# design.net
KiCad netlist of a schematic drawn in Altium Designer
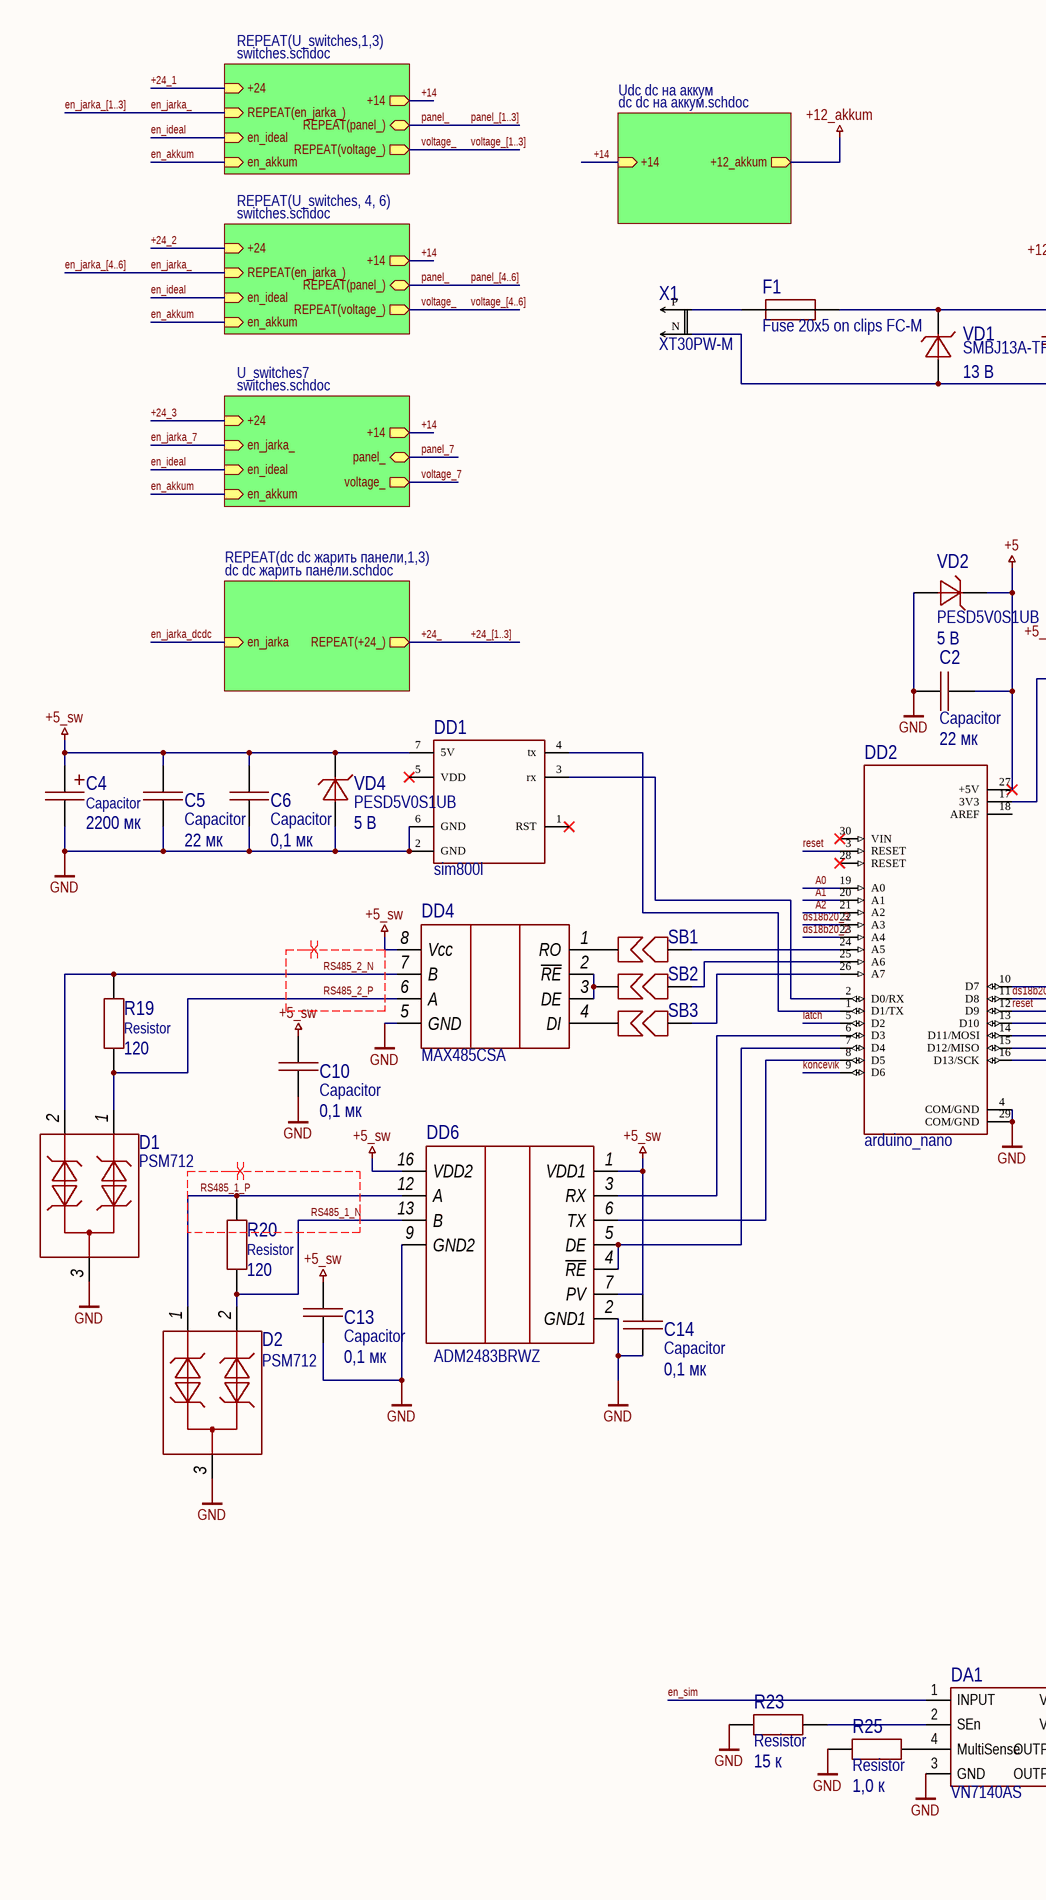
[diagram p0: хихема.SchDoc, left]
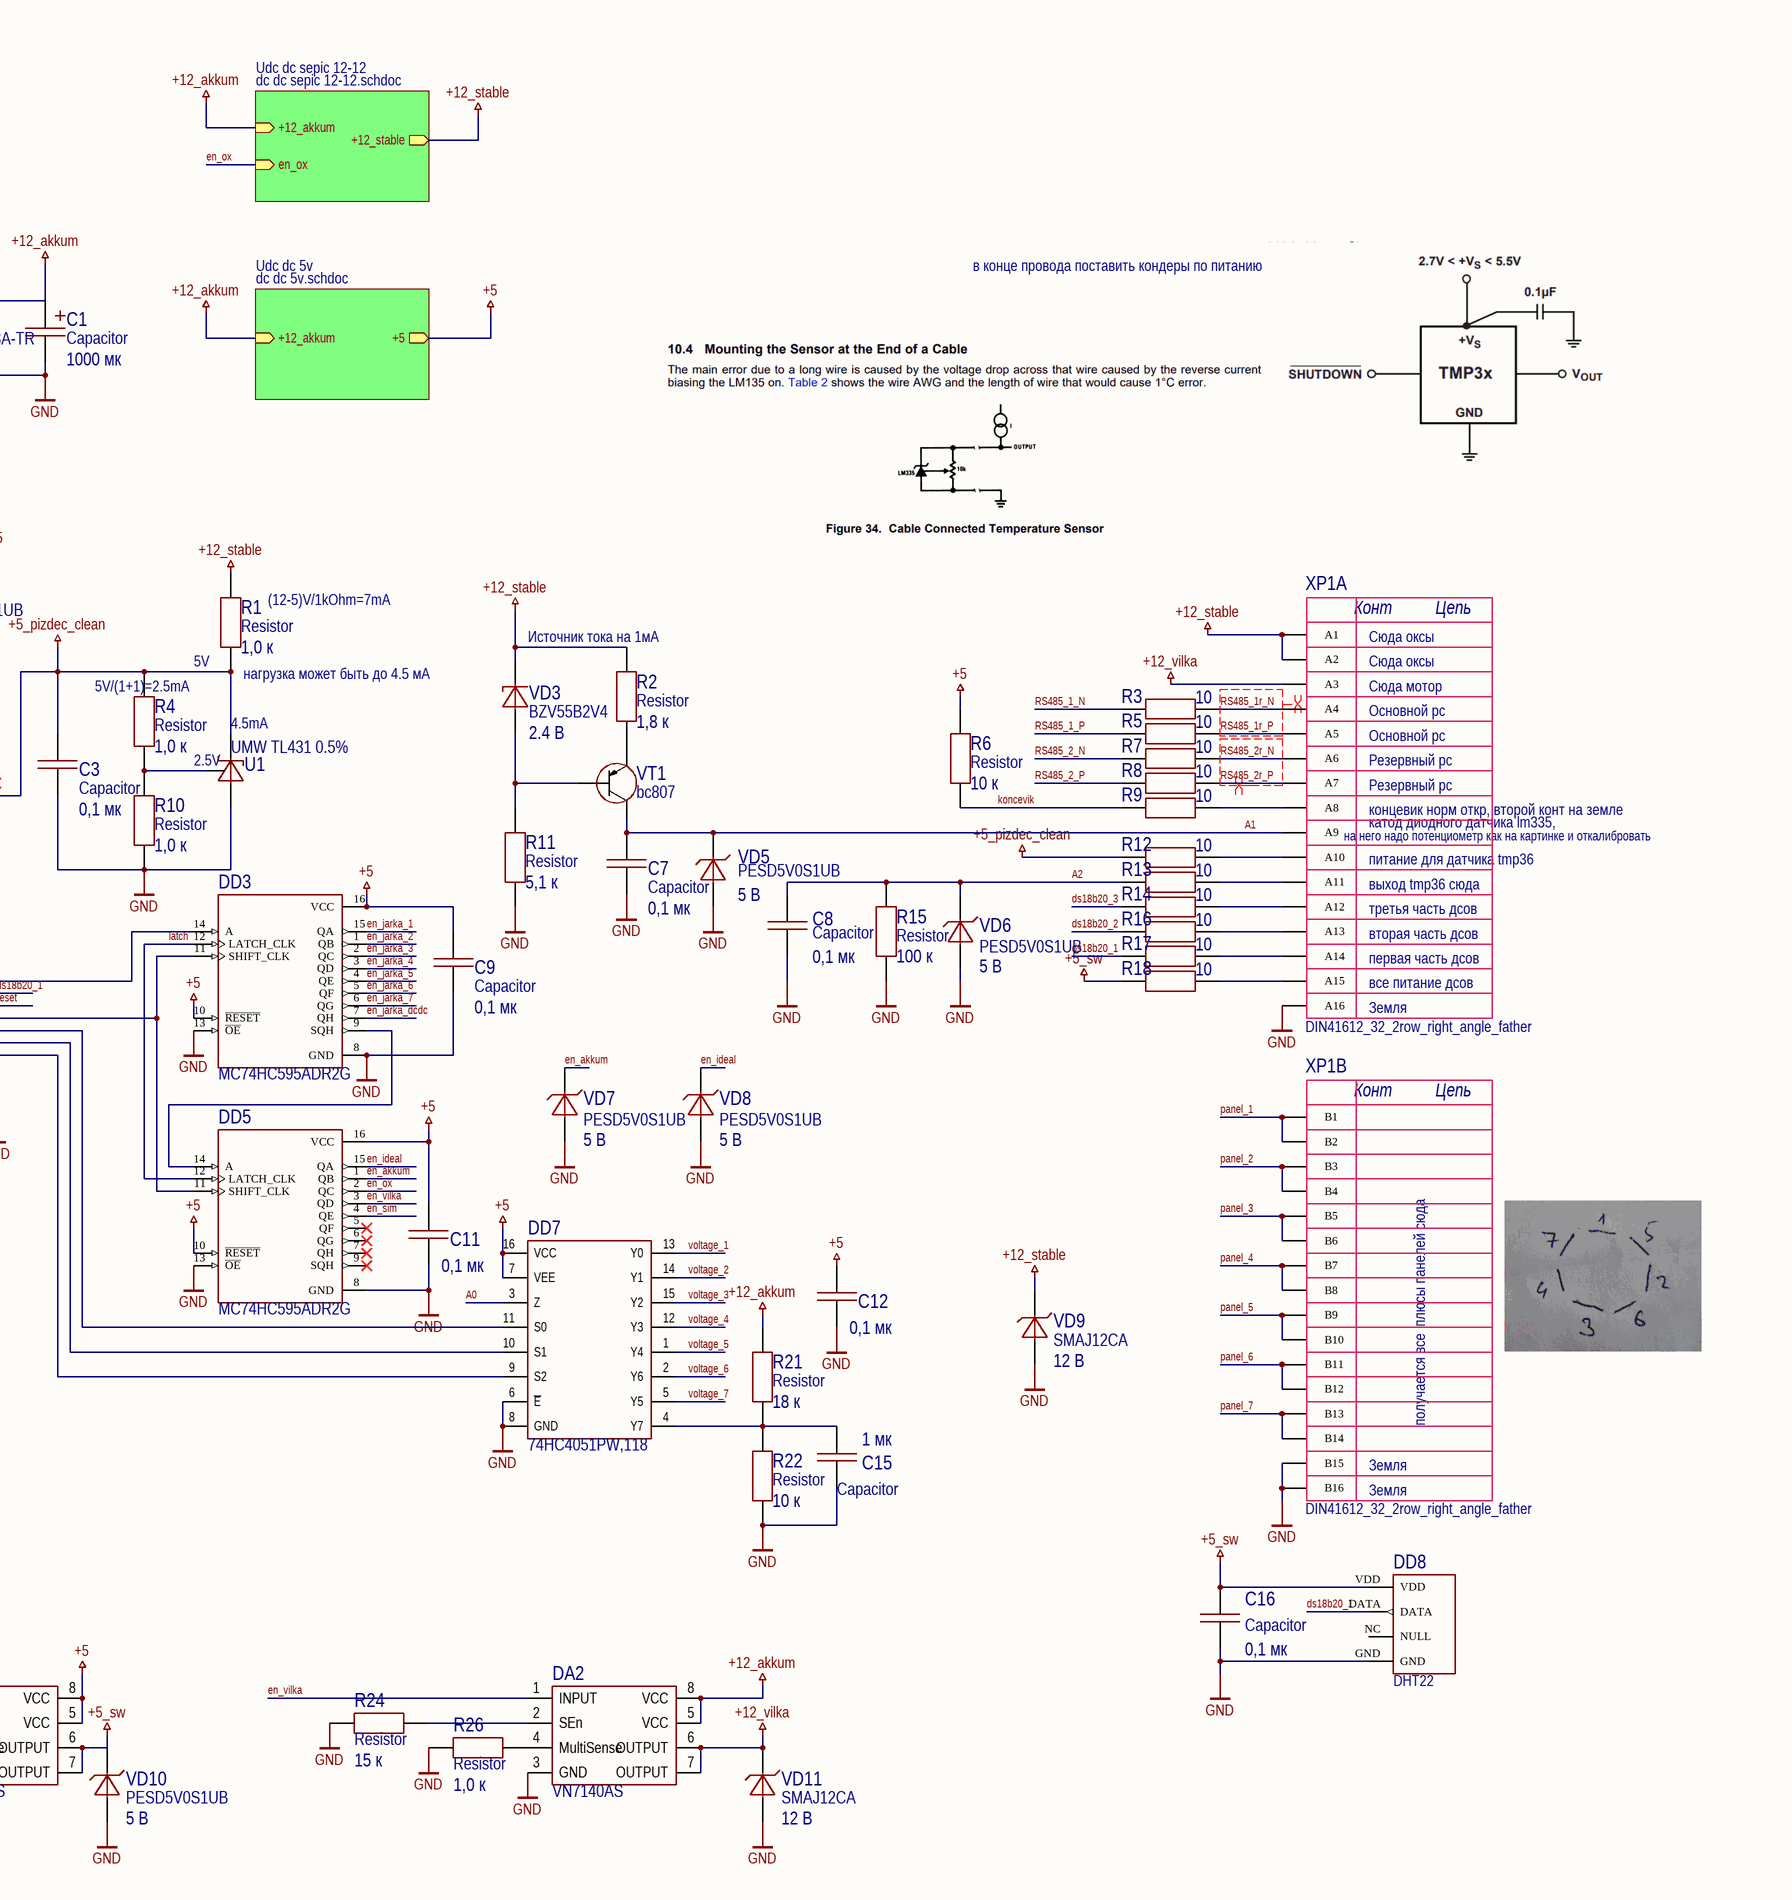
[diagram p1: хихема.SchDoc, right]

(export (version "E")
  (design (tool "Eeschema 10.0.6"))
  (components
    (comp (ref "C1")
      (value "Capacitor")
      (footprint "SMD_cap_12,5x13,5")
      (description "Конденсатор алюминиевый электролитический 1000мкФ 25В 20% Low ESR 1100мА SMD12.5x13.5мм")
      (fields
        (field (name "ALTIUM_VALUE") "1000 мк")
        (field (name "PART NUMBER") "EEVFK1E102Q")
        (field (name "TOLERANCE") "20")
      )
      (libsource (lib "Hydrolib") (part "Capacitor_polar"))
    )
    (comp (ref "C2")
      (value "Capacitor")
      (footprint "1210C")
      (description "Конденсатор")
      (fields
        (field (name "ALTIUM_VALUE") "22 мк")
        (field (name "PART NUMBER") "Capacitor_22u_10_25V_X7R_1210C")
        (field (name "TOLERANCE") "0,1")
      )
      (libsource (lib "Hydrolib") (part "Capacitor"))
    )
    (comp (ref "C3")
      (value "Capacitor")
      (footprint "0603C")
      (description "Конденсатор")
      (fields
        (field (name "ALTIUM_VALUE") "0,1 мк")
        (field (name "PART NUMBER") "Capacitor_0,1u_10_50V_X7R_0603C")
        (field (name "TOLERANCE") "0,1")
      )
      (libsource (lib "Hydrolib") (part "Capacitor"))
    )
    (comp (ref "C4")
      (value "Capacitor")
      (footprint "10x20_radial")
      (description "Конденсатор радиальный 2200мкФ 10В ±20% 10*19")
      (fields
        (field (name "ALTIUM_VALUE") "2200 мк")
        (field (name "PART NUMBER") "Capacitor_2200u_10V_10x20")
        (field (name "TOLERANCE") "20")
      )
      (libsource (lib "Hydrolib") (part "Capacitor_polar"))
    )
    (comp (ref "C5")
      (value "Capacitor")
      (footprint "1210C")
      (description "Конденсатор")
      (fields
        (field (name "ALTIUM_VALUE") "22 мк")
        (field (name "PART NUMBER") "Capacitor_22u_10_25V_X7R_1210C")
        (field (name "TOLERANCE") "0,1")
      )
      (libsource (lib "Hydrolib") (part "Capacitor"))
    )
    (comp (ref "C6")
      (value "Capacitor")
      (footprint "0603C")
      (description "Конденсатор")
      (fields
        (field (name "ALTIUM_VALUE") "0,1 мк")
        (field (name "PART NUMBER") "Capacitor_0,1u_10_50V_X7R_0603C")
        (field (name "TOLERANCE") "0,1")
      )
      (libsource (lib "Hydrolib") (part "Capacitor"))
    )
    (comp (ref "C7")
      (value "Capacitor")
      (footprint "0603C")
      (description "Конденсатор")
      (fields
        (field (name "ALTIUM_VALUE") "0,1 мк")
        (field (name "PART NUMBER") "Capacitor_0,1u_10_50V_X7R_0603C")
        (field (name "TOLERANCE") "0,1")
      )
      (libsource (lib "Hydrolib") (part "Capacitor"))
    )
    (comp (ref "C8")
      (value "Capacitor")
      (footprint "0603C")
      (description "Конденсатор")
      (fields
        (field (name "ALTIUM_VALUE") "0,1 мк")
        (field (name "PART NUMBER") "Capacitor_0,1u_10_50V_X7R_0603C")
        (field (name "TOLERANCE") "0,1")
      )
      (libsource (lib "Hydrolib") (part "Capacitor"))
    )
    (comp (ref "C9")
      (value "Capacitor")
      (footprint "0603C")
      (description "Конденсатор")
      (fields
        (field (name "ALTIUM_VALUE") "0,1 мк")
        (field (name "PART NUMBER") "Capacitor_0,1u_10_50V_X7R_0603C")
        (field (name "TOLERANCE") "0,1")
      )
      (libsource (lib "Hydrolib") (part "Capacitor"))
    )
    (comp (ref "C10")
      (value "Capacitor")
      (footprint "0603C")
      (description "Конденсатор")
      (fields
        (field (name "ALTIUM_VALUE") "0,1 мк")
        (field (name "PART NUMBER") "Capacitor_0,1u_10_50V_X7R_0603C")
        (field (name "TOLERANCE") "0,1")
      )
      (libsource (lib "Hydrolib") (part "Capacitor"))
    )
    (comp (ref "C11")
      (value "0,1 мк")
      (footprint "0603C")
      (description "Конденсатор")
      (fields (field (name "PART NUMBER") "Capacitor_0,1u_10_50V_X7R_0603C") (field (name "TOLERANCE") "0,1"))
      (libsource (lib "Hydrolib") (part "Capacitor"))
    )
    (comp (ref "C12")
      (value "0,1 мк")
      (footprint "0603C")
      (description "Конденсатор")
      (fields (field (name "PART NUMBER") "Capacitor_0,1u_10_50V_X7R_0603C") (field (name "TOLERANCE") "0,1"))
      (libsource (lib "Hydrolib") (part "Capacitor"))
    )
    (comp (ref "C13")
      (value "Capacitor")
      (footprint "0603C")
      (description "Конденсатор")
      (fields
        (field (name "ALTIUM_VALUE") "0,1 мк")
        (field (name "PART NUMBER") "Capacitor_0,1u_10_50V_X7R_0603C")
        (field (name "TOLERANCE") "0,1")
      )
      (libsource (lib "Hydrolib") (part "Capacitor"))
    )
    (comp (ref "C14")
      (value "Capacitor")
      (footprint "0603C")
      (description "Конденсатор")
      (fields
        (field (name "ALTIUM_VALUE") "0,1 мк")
        (field (name "PART NUMBER") "Capacitor_0,1u_10_50V_X7R_0603C")
        (field (name "TOLERANCE") "0,1")
      )
      (libsource (lib "Hydrolib") (part "Capacitor"))
    )
    (comp (ref "C15")
      (value "Capacitor")
      (footprint "0603C")
      (description "Конденсатор")
      (fields
        (field (name "ALTIUM_VALUE") "1 мк")
        (field (name "PART NUMBER") "Capacitor_1u_10_50V_X7R_0603C")
        (field (name "TOLERANCE") "0,1")
      )
      (libsource (lib "Hydrolib") (part "Capacitor"))
    )
    (comp (ref "C16")
      (value "Capacitor")
      (footprint "0603C")
      (description "Конденсатор")
      (fields
        (field (name "ALTIUM_VALUE") "0,1 мк")
        (field (name "PART NUMBER") "Capacitor_0,1u_10_50V_X7R_0603C")
        (field (name "TOLERANCE") "0,1")
      )
      (libsource (lib "Hydrolib") (part "Capacitor"))
    )
    (comp (ref "D1")
      (value "PSM712")
      (footprint "SOT23-3")
      (description "Защитный диод для линии RS-485")
      (libsource (lib "") (part "TVS_2_2dir_1"))
    )
    (comp (ref "D2")
      (value "PSM712")
      (footprint "SOT23-3")
      (description "Защитный диод для линии RS-485")
      (libsource (lib "Hydrolib") (part "TVS_2_2dir"))
    )
    (comp (ref "DA1")
      (value "VN7140AS")
      (footprint "SOP8")
      (description "Силовой ключ верхнего плеча с аналоговой обратной связью MultiSense автомобильного применения")
      (libsource (lib "Hydrolib") (part "VN7140AS"))
    )
    (comp (ref "DA2")
      (value "VN7140AS")
      (footprint "SOP8")
      (description "Силовой ключ верхнего плеча с аналоговой обратной связью MultiSense автомобильного применения")
      (libsource (lib "Hydrolib") (part "VN7140AS"))
    )
    (comp (ref "DD1") (value "sim800l") (footprint "sim800l") (libsource (lib "Hydrolib") (part "sim800l")))
    (comp (ref "DD2")
      (value "arduino_nano")
      (footprint "arduino_nano")
      (description "ардуинка на стойках")
      (fields (field (name "MP") "Arduino Nano") (field (name "MF") "Arduino"))
      (libsource (lib "Hydrolib") (part "ARDUINO_NANO"))
    )
    (comp (ref "DD3")
      (value "MC74HC595ADR2G")
      (footprint "SOIC-16")
      (description "8-ми битный сдвиговый регистр")
      (libsource (lib "Hydrolib") (part "MC74HC595ADR2G"))
    )
    (comp (ref "DD4")
      (value "MAX485CSA")
      (footprint "SOIC-8")
      (description "RS-485 приёмопередатчик")
      (libsource (lib "Hydrolib") (part "MAX485CSA"))
    )
    (comp (ref "DD5")
      (value "MC74HC595ADR2G")
      (footprint "SOIC-16")
      (description "8-ми битный сдвиговый регистр")
      (libsource (lib "Hydrolib") (part "MC74HC595ADR2G"))
    )
    (comp (ref "DD6")
      (value "ADM2483BRWZ")
      (footprint "SOIC-16W")
      (description "Прием передатчик RS485 с гальванической развязкой")
      (libsource (lib "Hydrolib") (part "ADM2483BRWZ"))
    )
    (comp (ref "DD7")
      (value "74HC4051PW,118")
      (footprint "TSSOP-16")
      (description "Мультиплексор аналоговый 8 в 1 КМОП кристалл, TSSOP16")
      (libsource (lib "Hydrolib") (part "74HC4051PW,118"))
    )
    (comp (ref "DD8")
      (value "DHT22")
      (footprint "DHT22")
      (description "Датчик температуры и влажности на базе AM2302")
      (libsource (lib "Hydrolib") (part "DHT22"))
    )
    (comp (ref "F1")
      (value "Fuse 20x5 on clips FC-M")
      (footprint "fuse_20x5_on_clips_FC-M")
      (description "Предохранитель 20*5 на креплениях")
      (libsource (lib "Hydrolib") (part "Fuse"))
    )
    (comp (ref "R1")
      (value "Resistor")
      (footprint "0603R")
      (description "Резистор номиналом 1,0 кОм и точностью 1%")
      (fields
        (field (name "ALTIUM_VALUE") "1,0 к")
        (field (name "PART NUMBER") "Resistor_1.0k_1_0603")
        (field (name "TOLERANCE") "1%")
      )
      (libsource (lib "Hydrolib") (part "Resistor"))
    )
    (comp (ref "R2")
      (value "Resistor")
      (footprint "0603R")
      (description "Резистор номиналом 1,8 кОм и точностью 1%")
      (fields
        (field (name "ALTIUM_VALUE") "1,8 к")
        (field (name "PART NUMBER") "Resistor_1.8k_1_0603")
        (field (name "TOLERANCE") "1%")
      )
      (libsource (lib "Hydrolib") (part "Resistor"))
    )
    (comp (ref "R3")
      (value "10")
      (footprint "0603R")
      (description "Резистор номиналом 10 Ом и точностью 1%")
      (fields (field (name "PART NUMBER") "Resistor_10_1_0603") (field (name "TOLERANCE") "1%"))
      (libsource (lib "") (part "Resistor_1"))
    )
    (comp (ref "R4")
      (value "Resistor")
      (footprint "0603R")
      (description "Резистор номиналом 1,0 кОм и точностью 1%")
      (fields
        (field (name "ALTIUM_VALUE") "1,0 к")
        (field (name "PART NUMBER") "Resistor_1.0k_1_0603")
        (field (name "TOLERANCE") "1%")
      )
      (libsource (lib "Hydrolib") (part "Resistor"))
    )
    (comp (ref "R5")
      (value "10")
      (footprint "0603R")
      (description "Резистор номиналом 10 Ом и точностью 1%")
      (fields (field (name "PART NUMBER") "Resistor_10_1_0603") (field (name "TOLERANCE") "1%"))
      (libsource (lib "") (part "Resistor_1"))
    )
    (comp (ref "R6")
      (value "Resistor")
      (footprint "0603R")
      (description "Резистор номиналом 10 кОм и точностью 1%")
      (fields
        (field (name "ALTIUM_VALUE") "10 к")
        (field (name "PART NUMBER") "Resistor_10k_1_0603")
        (field (name "TOLERANCE") "1%")
      )
      (libsource (lib "Hydrolib") (part "Resistor"))
    )
    (comp (ref "R7")
      (value "10")
      (footprint "0603R")
      (description "Резистор номиналом 10 Ом и точностью 1%")
      (fields (field (name "PART NUMBER") "Resistor_10_1_0603") (field (name "TOLERANCE") "1%"))
      (libsource (lib "") (part "Resistor_1"))
    )
    (comp (ref "R8")
      (value "10")
      (footprint "0603R")
      (description "Резистор номиналом 10 Ом и точностью 1%")
      (fields (field (name "PART NUMBER") "Resistor_10_1_0603") (field (name "TOLERANCE") "1%"))
      (libsource (lib "") (part "Resistor_1"))
    )
    (comp (ref "R9")
      (value "10")
      (footprint "0603R")
      (description "Резистор номиналом 10 Ом и точностью 1%")
      (fields (field (name "PART NUMBER") "Resistor_10_1_0603") (field (name "TOLERANCE") "1%"))
      (libsource (lib "") (part "Resistor_1"))
    )
    (comp (ref "R10")
      (value "Resistor")
      (footprint "0603R")
      (description "Резистор номиналом 1,0 кОм и точностью 1%")
      (fields
        (field (name "ALTIUM_VALUE") "1,0 к")
        (field (name "PART NUMBER") "Resistor_1.0k_1_0603")
        (field (name "TOLERANCE") "1%")
      )
      (libsource (lib "Hydrolib") (part "Resistor"))
    )
    (comp (ref "R11")
      (value "Resistor")
      (footprint "0603R")
      (description "Резистор номиналом 5,1 кОм и точностью 1%")
      (fields
        (field (name "ALTIUM_VALUE") "5,1 к")
        (field (name "PART NUMBER") "Resistor_5.1k_1_0603")
        (field (name "TOLERANCE") "1%")
      )
      (libsource (lib "Hydrolib") (part "Resistor"))
    )
    (comp (ref "R12")
      (value "10")
      (footprint "0603R")
      (description "Резистор номиналом 10 Ом и точностью 1%")
      (fields (field (name "PART NUMBER") "Resistor_10_1_0603") (field (name "TOLERANCE") "1%"))
      (libsource (lib "") (part "Resistor_1"))
    )
    (comp (ref "R13")
      (value "10")
      (footprint "0603R")
      (description "Резистор номиналом 10 Ом и точностью 1%")
      (fields (field (name "PART NUMBER") "Resistor_10_1_0603") (field (name "TOLERANCE") "1%"))
      (libsource (lib "") (part "Resistor_1"))
    )
    (comp (ref "R14")
      (value "10")
      (footprint "0603R")
      (description "Резистор номиналом 10 Ом и точностью 1%")
      (fields (field (name "PART NUMBER") "Resistor_10_1_0603") (field (name "TOLERANCE") "1%"))
      (libsource (lib "") (part "Resistor_1"))
    )
    (comp (ref "R15")
      (value "Resistor")
      (footprint "0603R")
      (description "Резистор номиналом 100 кОм и точностью 1%")
      (fields
        (field (name "ALTIUM_VALUE") "100 к")
        (field (name "PART NUMBER") "Resistor_100k_1_0603")
        (field (name "TOLERANCE") "1%")
      )
      (libsource (lib "Hydrolib") (part "Resistor"))
    )
    (comp (ref "R16")
      (value "10")
      (footprint "0603R")
      (description "Резистор номиналом 10 Ом и точностью 1%")
      (fields (field (name "PART NUMBER") "Resistor_10_1_0603") (field (name "TOLERANCE") "1%"))
      (libsource (lib "") (part "Resistor_1"))
    )
    (comp (ref "R17")
      (value "10")
      (footprint "0603R")
      (description "Резистор номиналом 10 Ом и точностью 1%")
      (fields (field (name "PART NUMBER") "Resistor_10_1_0603") (field (name "TOLERANCE") "1%"))
      (libsource (lib "") (part "Resistor_1"))
    )
    (comp (ref "R18")
      (value "10")
      (footprint "0603R")
      (description "Резистор номиналом 10 Ом и точностью 1%")
      (fields (field (name "PART NUMBER") "Resistor_10_1_0603") (field (name "TOLERANCE") "1%"))
      (libsource (lib "") (part "Resistor_1"))
    )
    (comp (ref "R19")
      (value "Resistor")
      (footprint "1206R")
      (description "Резистор номиналом 120 Ом и точностью 1%")
      (fields
        (field (name "ALTIUM_VALUE") "120")
        (field (name "PART NUMBER") "Resistor_120_1_0603")
        (field (name "TOLERANCE") "1%")
      )
      (libsource (lib "Hydrolib") (part "Resistor"))
    )
    (comp (ref "R20")
      (value "Resistor")
      (footprint "1206R")
      (description "Резистор номиналом 120 Ом и точностью 1%")
      (fields
        (field (name "ALTIUM_VALUE") "120")
        (field (name "PART NUMBER") "Resistor_120_1_0603")
        (field (name "TOLERANCE") "1%")
      )
      (libsource (lib "Hydrolib") (part "Resistor"))
    )
    (comp (ref "R21")
      (value "Resistor")
      (footprint "0603R")
      (description "Резистор номиналом 18 кОм и точностью 1%")
      (fields
        (field (name "ALTIUM_VALUE") "18 к")
        (field (name "PART NUMBER") "Resistor_18k_1_0603")
        (field (name "TOLERANCE") "1%")
      )
      (libsource (lib "Hydrolib") (part "Resistor"))
    )
    (comp (ref "R22")
      (value "Resistor")
      (footprint "0603R")
      (description "Резистор номиналом 10 кОм и точностью 1%")
      (fields
        (field (name "ALTIUM_VALUE") "10 к")
        (field (name "PART NUMBER") "Resistor_10k_1_0603")
        (field (name "TOLERANCE") "1%")
      )
      (libsource (lib "Hydrolib") (part "Resistor"))
    )
    (comp (ref "R23")
      (value "Resistor")
      (footprint "0603R")
      (description "Резистор номиналом 15 кОм и точностью 1%")
      (fields
        (field (name "ALTIUM_VALUE") "15 к")
        (field (name "PART NUMBER") "Resistor_15k_1_0603")
        (field (name "TOLERANCE") "1%")
      )
      (libsource (lib "") (part "Resistor_1"))
    )
    (comp (ref "R24")
      (value "Resistor")
      (footprint "0603R")
      (description "Резистор номиналом 15 кОм и точностью 1%")
      (fields
        (field (name "ALTIUM_VALUE") "15 к")
        (field (name "PART NUMBER") "Resistor_15k_1_0603")
        (field (name "TOLERANCE") "1%")
      )
      (libsource (lib "") (part "Resistor_1"))
    )
    (comp (ref "R25")
      (value "Resistor")
      (footprint "0603R")
      (description "Резистор номиналом 1,0 кОм и точностью 1%")
      (fields
        (field (name "ALTIUM_VALUE") "1,0 к")
        (field (name "PART NUMBER") "Resistor_1.0k_1_0603")
        (field (name "TOLERANCE") "1%")
      )
      (libsource (lib "") (part "Resistor_1"))
    )
    (comp (ref "R26")
      (value "Resistor")
      (footprint "0603R")
      (description "Резистор номиналом 1,0 кОм и точностью 1%")
      (fields
        (field (name "ALTIUM_VALUE") "1,0 к")
        (field (name "PART NUMBER") "Resistor_1.0k_1_0603")
        (field (name "TOLERANCE") "1%")
      )
      (libsource (lib "") (part "Resistor_1"))
    )
    (comp (ref "SB1")
      (value "SB")
      (footprint "0805SB")
      (description "Solder bridge, мост припоя, запаиваемая перемычка, net tie, jumper")
      (libsource (lib "Hydrolib") (part "SB"))
    )
    (comp (ref "SB2")
      (value "SB")
      (footprint "0805SB")
      (description "Solder bridge, мост припоя, запаиваемая перемычка, net tie, jumper")
      (libsource (lib "Hydrolib") (part "SB"))
    )
    (comp (ref "SB3")
      (value "SB")
      (footprint "0805SB")
      (description "Solder bridge, мост припоя, запаиваемая перемычка, net tie, jumper")
      (libsource (lib "Hydrolib") (part "SB"))
    )
    (comp (ref "U1")
      (value "UMW TL431 0.5%")
      (footprint "SOT23-3")
      (description "Источник опорного напряжения , программируемый стабилитрон [SOT-23-3]")
      (libsource (lib "Hydrolib") (part "precision_shunt_regulator"))
    )
    (comp (ref "VD1")
      (value "SMBJ13A-TR")
      (footprint "SMB")
      (description "Защитный диод на 13 В, рассеиваемая мощность 600 Вт")
      (fields (field (name "ALTIUM_VALUE") "13 В"))
      (libsource (lib "Hydrolib") (part "TVS_1_1dir"))
    )
    (comp (ref "VD2")
      (value "PESD5V0S1UB")
      (footprint "SOD523")
      (description "Защитный диод на 5 В, рассеиваемая мощность 330 Вт")
      (fields (field (name "ALTIUM_VALUE") "5 В"))
      (libsource (lib "Hydrolib") (part "TVS_1_1dir"))
    )
    (comp (ref "VD3")
      (value "BZV55B2V4")
      (footprint "mini_MELF_3.5mm")
      (description "Стабилитрон на 2.4 В, рассеиваемая мощность 0.5 Вт")
      (fields (field (name "ALTIUM_VALUE") "2.4 В"))
      (libsource (lib "Hydrolib") (part "Zener"))
    )
    (comp (ref "VD4")
      (value "PESD5V0S1UB")
      (footprint "SOD523")
      (description "Защитный диод на 5 В, рассеиваемая мощность 330 Вт")
      (fields (field (name "ALTIUM_VALUE") "5 В"))
      (libsource (lib "Hydrolib") (part "TVS_1_1dir"))
    )
    (comp (ref "VD5")
      (value "PESD5V0S1UB")
      (footprint "SOD523")
      (description "Защитный диод на 5 В, рассеиваемая мощность 330 Вт")
      (fields (field (name "ALTIUM_VALUE") "5 В"))
      (libsource (lib "Hydrolib") (part "TVS_1_1dir"))
    )
    (comp (ref "VD6")
      (value "PESD5V0S1UB")
      (footprint "SOD523")
      (description "Защитный диод на 5 В, рассеиваемая мощность 330 Вт")
      (fields (field (name "ALTIUM_VALUE") "5 В"))
      (libsource (lib "Hydrolib") (part "TVS_1_1dir"))
    )
    (comp (ref "VD7")
      (value "PESD5V0S1UB")
      (footprint "SOD523")
      (description "Защитный диод на 5 В, рассеиваемая мощность 330 Вт")
      (fields (field (name "ALTIUM_VALUE") "5 В"))
      (libsource (lib "Hydrolib") (part "TVS_1_1dir"))
    )
    (comp (ref "VD8")
      (value "PESD5V0S1UB")
      (footprint "SOD523")
      (description "Защитный диод на 5 В, рассеиваемая мощность 330 Вт")
      (fields (field (name "ALTIUM_VALUE") "5 В"))
      (libsource (lib "Hydrolib") (part "TVS_1_1dir"))
    )
    (comp (ref "VD9")
      (value "SMAJ12CA")
      (footprint "SMA")
      (description "Защитный диод на 12 В, рассеиваемая мощность 400 Вт")
      (fields (field (name "ALTIUM_VALUE") "12 В"))
      (libsource (lib "Hydrolib") (part "TVS_1_1dir"))
    )
    (comp (ref "VD10")
      (value "PESD5V0S1UB")
      (footprint "SOD523")
      (description "Защитный диод на 5 В, рассеиваемая мощность 330 Вт")
      (fields (field (name "ALTIUM_VALUE") "5 В"))
      (libsource (lib "Hydrolib") (part "TVS_1_1dir"))
    )
    (comp (ref "VD11")
      (value "SMAJ12CA")
      (footprint "SMA")
      (description "Защитный диод на 12 В, рассеиваемая мощность 400 Вт")
      (fields (field (name "ALTIUM_VALUE") "12 В"))
      (libsource (lib "Hydrolib") (part "TVS_1_1dir"))
    )
    (comp (ref "VT1")
      (value "bc807")
      (footprint "SOT23-3")
      (description "Биполярный транзистор PNP 45В 0.5А 0.31Вт")
      (libsource (lib "Hydrolib") (part "pnp"))
    )
    (comp (ref "X1")
      (value "XT30PW-M")
      (footprint "XT30PW-M")
      (description "30 А (15 продолжительно), 2 контакта разъем угловой отец")
      (libsource (lib "Hydrolib") (part "Polar_Conn"))
    )
    (comp (ref "XP1")
      (value "DIN41612_32_2row_right_angle_father")
      (footprint "DIN41612_32_2row_right_angle_father")
      (libsource (lib "") (part "DIN41612_32_2row_1"))
    )
  )
  (nets
    (net (code "1") (name "+5") (class "Default")
      (node (ref "C11") (pin "2") (pinfunction "2_2") (pintype "passive"))
      (node (ref "C12") (pin "2") (pinfunction "2_2") (pintype "passive"))
      (node (ref "C2") (pin "1") (pinfunction "1_1") (pintype "passive"))
      (node (ref "C9") (pin "2") (pinfunction "2_2") (pintype "passive"))
      (node (ref "DA1") (pin "5") (pinfunction "VCC_5") (pintype "passive"))
      (node (ref "DA1") (pin "8") (pinfunction "VCC_8") (pintype "passive"))
      (node (ref "DD2") (pin "27") (pinfunction "+5V_27") (pintype "power_in"))
      (node (ref "DD3") (pin "10") (pinfunction "~{RESET}_10") (pintype "input"))
      (node (ref "DD3") (pin "16") (pinfunction "VCC_16") (pintype "power_in"))
      (node (ref "DD5") (pin "10") (pinfunction "~{RESET}_10") (pintype "input"))
      (node (ref "DD5") (pin "16") (pinfunction "VCC_16") (pintype "power_in"))
      (node (ref "DD7") (pin "16") (pinfunction "VCC_16") (pintype "passive"))
      (node (ref "DD7") (pin "7") (pinfunction "VEE_7") (pintype "passive"))
      (node (ref "R6") (pin "2") (pinfunction "2_2") (pintype "passive"))
      (node (ref "VD2") (pin "2") (pinfunction "2_2") (pintype "passive"))
    )
    (net (code "2") (name "+5_pizdec_clean") (class "Default")
      (node (ref "C3") (pin "2") (pinfunction "2_2") (pintype "passive"))
      (node (ref "DD2") (pin "17") (pinfunction "3V3_17") (pintype "power_in"))
      (node (ref "R1") (pin "1") (pinfunction "1_1") (pintype "passive"))
      (node (ref "R12") (pin "1") (pinfunction "1_1") (pintype "passive"))
      (node (ref "R4") (pin "2") (pinfunction "2_2") (pintype "passive"))
      (node (ref "U1") (pin "2") (pinfunction "2_2") (pintype "passive"))
    )
    (net (code "3") (name "+5_sw") (class "Default")
      (node (ref "C10") (pin "1") (pinfunction "1_1") (pintype "passive"))
      (node (ref "C13") (pin "2") (pinfunction "2_2") (pintype "passive"))
      (node (ref "C14") (pin "2") (pinfunction "2_2") (pintype "passive"))
      (node (ref "C16") (pin "2") (pinfunction "2_2") (pintype "passive"))
      (node (ref "C4") (pin "1") (pinfunction "1_1") (pintype "passive"))
      (node (ref "C5") (pin "2") (pinfunction "2_2") (pintype "passive"))
      (node (ref "C6") (pin "2") (pinfunction "2_2") (pintype "passive"))
      (node (ref "DA1") (pin "6") (pinfunction "OUTPUT_6") (pintype "passive"))
      (node (ref "DA1") (pin "7") (pinfunction "OUTPUT_7") (pintype "passive"))
      (node (ref "DD1") (pin "7") (pinfunction "5V_7") (pintype "passive"))
      (node (ref "DD4") (pin "8") (pinfunction "Vcc_8") (pintype "passive"))
      (node (ref "DD6") (pin "1") (pinfunction "VDD1_1") (pintype "passive"))
      (node (ref "DD6") (pin "16") (pinfunction "VDD2_16") (pintype "passive"))
      (node (ref "DD6") (pin "7") (pinfunction "PV_7") (pintype "passive"))
      (node (ref "DD8") (pin "VDD") (pinfunction "VDD_VDD") (pintype "power_in"))
      (node (ref "R18") (pin "1") (pinfunction "1_1") (pintype "passive"))
      (node (ref "VD10") (pin "2") (pinfunction "2_2") (pintype "passive"))
      (node (ref "VD4") (pin "2") (pinfunction "2_2") (pintype "passive"))
    )
    (net (code "4") (name "+12_akkum") (class "Default")
      (node (ref "C1") (pin "1") (pinfunction "1_1") (pintype "passive"))
      (node (ref "DA2") (pin "5") (pinfunction "VCC_5") (pintype "passive"))
      (node (ref "DA2") (pin "8") (pinfunction "VCC_8") (pintype "passive"))
      (node (ref "F1") (pin "2") (pinfunction "2_2") (pintype "passive"))
      (node (ref "R21") (pin "2") (pinfunction "2_2") (pintype "passive"))
      (node (ref "VD1") (pin "2") (pinfunction "2_2") (pintype "passive"))
    )
    (net (code "5") (name "+12_stable") (class "Default")
      (node (ref "R1") (pin "2") (pinfunction "2_2") (pintype "passive"))
      (node (ref "R2") (pin "2") (pinfunction "2_2") (pintype "passive"))
      (node (ref "VD3") (pin "2") (pinfunction "2_2") (pintype "passive"))
      (node (ref "VD9") (pin "2") (pinfunction "2_2") (pintype "passive"))
      (node (ref "XP1") (pin "A1") (pinfunction "A1_A1") (pintype "passive"))
      (node (ref "XP1") (pin "A2") (pinfunction "A2_A2") (pintype "passive"))
    )
    (net (code "6") (name "+12_vilka") (class "Default")
      (node (ref "DA2") (pin "6") (pinfunction "OUTPUT_6") (pintype "passive"))
      (node (ref "DA2") (pin "7") (pinfunction "OUTPUT_7") (pintype "passive"))
      (node (ref "VD11") (pin "2") (pinfunction "2_2") (pintype "passive"))
      (node (ref "XP1") (pin "A3") (pinfunction "A3_A3") (pintype "passive"))
    )
    (net (code "13") (name "/A0") (class "Default")
      (node (ref "DD2") (pin "19") (pinfunction "A0_19") (pintype "input"))
      (node (ref "DD7") (pin "3") (pinfunction "Z_3") (pintype "passive"))
    )
    (net (code "14") (name "/A1") (class "Default")
      (node (ref "C7") (pin "2") (pinfunction "2_2") (pintype "passive"))
      (node (ref "DD2") (pin "20") (pinfunction "A1_20") (pintype "input"))
      (node (ref "VD5") (pin "2") (pinfunction "2_2") (pintype "passive"))
      (node (ref "VT1") (pin "3") (pinfunction "3_3") (pintype "passive"))
      (node (ref "XP1") (pin "A9") (pinfunction "A9_A9") (pintype "passive"))
    )
    (net (code "15") (name "/A2") (class "Default")
      (node (ref "C8") (pin "2") (pinfunction "2_2") (pintype "passive"))
      (node (ref "DD2") (pin "21") (pinfunction "A2_21") (pintype "input"))
      (node (ref "R13") (pin "1") (pinfunction "1_1") (pintype "passive"))
      (node (ref "R15") (pin "2") (pinfunction "2_2") (pintype "passive"))
      (node (ref "VD6") (pin "2") (pinfunction "2_2") (pintype "passive"))
    )
    (net (code "16") (name "/RS485_1_N") (class "Default")
      (node (ref "D2") (pin "2") (pinfunction "15_2") (pintype "passive"))
      (node (ref "DD6") (pin "13") (pinfunction "B_13") (pintype "passive"))
      (node (ref "R20") (pin "1") (pinfunction "1_1") (pintype "passive"))
      (node (ref "R3") (pin "1") (pinfunction "1_1") (pintype "passive"))
    )
    (net (code "17") (name "/RS485_1_P") (class "Default")
      (node (ref "D2") (pin "1") (pinfunction "14_1") (pintype "passive"))
      (node (ref "DD6") (pin "12") (pinfunction "A_12") (pintype "passive"))
      (node (ref "R20") (pin "2") (pinfunction "2_2") (pintype "passive"))
      (node (ref "R5") (pin "1") (pinfunction "1_1") (pintype "passive"))
    )
    (net (code "18") (name "/RS485_1r_N") (class "Default")
      (node (ref "R3") (pin "2") (pinfunction "2_2") (pintype "passive"))
      (node (ref "XP1") (pin "A4") (pinfunction "A4_A4") (pintype "passive"))
    )
    (net (code "19") (name "/RS485_1r_P") (class "Default")
      (node (ref "R5") (pin "2") (pinfunction "2_2") (pintype "passive"))
      (node (ref "XP1") (pin "A5") (pinfunction "A5_A5") (pintype "passive"))
    )
    (net (code "20") (name "/RS485_2_N") (class "Default")
      (node (ref "D1") (pin "2") (pinfunction "15_2") (pintype "passive"))
      (node (ref "DD4") (pin "7") (pinfunction "B_7") (pintype "passive"))
      (node (ref "R19") (pin "2") (pinfunction "2_2") (pintype "passive"))
      (node (ref "R7") (pin "1") (pinfunction "1_1") (pintype "passive"))
    )
    (net (code "21") (name "/RS485_2_P") (class "Default")
      (node (ref "D1") (pin "1") (pinfunction "14_1") (pintype "passive"))
      (node (ref "DD4") (pin "6") (pinfunction "A_6") (pintype "passive"))
      (node (ref "R19") (pin "1") (pinfunction "1_1") (pintype "passive"))
      (node (ref "R8") (pin "1") (pinfunction "1_1") (pintype "passive"))
    )
    (net (code "22") (name "/RS485_2r_N") (class "Default")
      (node (ref "R7") (pin "2") (pinfunction "2_2") (pintype "passive"))
      (node (ref "XP1") (pin "A6") (pinfunction "A6_A6") (pintype "passive"))
    )
    (net (code "23") (name "/RS485_2r_P") (class "Default")
      (node (ref "R8") (pin "2") (pinfunction "2_2") (pintype "passive"))
      (node (ref "XP1") (pin "A7") (pinfunction "A7_A7") (pintype "passive"))
    )
    (net (code "24") (name "/ds18b20_1") (class "Default")
      (node (ref "DD2") (pin "11") (pinfunction "D8_11") (pintype "bidirectional"))
      (node (ref "DD8") (pin "DATA") (pinfunction "DATA_DATA") (pintype "output"))
      (node (ref "R17") (pin "1") (pinfunction "1_1") (pintype "passive"))
    )
    (net (code "25") (name "/ds18b20_2") (class "Default")
      (node (ref "DD2") (pin "23") (pinfunction "A4_23") (pintype "input"))
      (node (ref "R16") (pin "1") (pinfunction "1_1") (pintype "passive"))
    )
    (net (code "26") (name "/ds18b20_3") (class "Default")
      (node (ref "DD2") (pin "22") (pinfunction "A3_22") (pintype "input"))
      (node (ref "R14") (pin "1") (pinfunction "1_1") (pintype "passive"))
    )
    (net (code "27") (name "/en_akkum") (class "Default")
      (node (ref "DD5") (pin "1") (pinfunction "QB_1") (pintype "output"))
      (node (ref "VD7") (pin "2") (pinfunction "2_2") (pintype "passive"))
    )
    (net (code "28") (name "/en_ideal") (class "Default")
      (node (ref "DD5") (pin "15") (pinfunction "QA_15") (pintype "output"))
      (node (ref "VD8") (pin "2") (pinfunction "2_2") (pintype "passive"))
    )
    (net (code "30") (name "/en_jarka_1") (class "Default")
      (node (ref "DD3") (pin "15") (pinfunction "QA_15") (pintype "output"))
    )
    (net (code "31") (name "/en_jarka_2") (class "Default")
      (node (ref "DD3") (pin "1") (pinfunction "QB_1") (pintype "output"))
    )
    (net (code "32") (name "/en_jarka_3") (class "Default")
      (node (ref "DD3") (pin "2") (pinfunction "QC_2") (pintype "output"))
    )
    (net (code "33") (name "/en_jarka_4") (class "Default")
      (node (ref "DD3") (pin "3") (pinfunction "QD_3") (pintype "output"))
    )
    (net (code "34") (name "/en_jarka_5") (class "Default")
      (node (ref "DD3") (pin "4") (pinfunction "QE_4") (pintype "output"))
    )
    (net (code "35") (name "/en_jarka_6") (class "Default")
      (node (ref "DD3") (pin "5") (pinfunction "QF_5") (pintype "output"))
    )
    (net (code "36") (name "/en_jarka_7") (class "Default")
      (node (ref "DD3") (pin "6") (pinfunction "QG_6") (pintype "output"))
    )
    (net (code "39") (name "/en_jarka_dcdc") (class "Default")
      (node (ref "DD3") (pin "7") (pinfunction "QH_7") (pintype "output"))
    )
    (net (code "40") (name "/en_ox") (class "Default")
      (node (ref "DD5") (pin "2") (pinfunction "QC_2") (pintype "output"))
    )
    (net (code "41") (name "/en_sim") (class "Default")
      (node (ref "DA1") (pin "1") (pinfunction "INPUT_1") (pintype "passive"))
      (node (ref "DD5") (pin "4") (pinfunction "QE_4") (pintype "output"))
    )
    (net (code "42") (name "/en_vilka") (class "Default")
      (node (ref "DA2") (pin "1") (pinfunction "INPUT_1") (pintype "passive"))
      (node (ref "DD5") (pin "3") (pinfunction "QD_3") (pintype "output"))
    )
    (net (code "43") (name "/koncevik") (class "Default")
      (node (ref "DD2") (pin "9") (pinfunction "D6_9") (pintype "bidirectional"))
      (node (ref "R6") (pin "1") (pinfunction "1_1") (pintype "passive"))
      (node (ref "R9") (pin "1") (pinfunction "1_1") (pintype "passive"))
    )
    (net (code "44") (name "/latch") (class "Default")
      (node (ref "DD2") (pin "5") (pinfunction "D2_5") (pintype "bidirectional"))
      (node (ref "DD3") (pin "12") (pinfunction "LATCH_CLK_12") (pintype "input"))
      (node (ref "DD5") (pin "12") (pinfunction "LATCH_CLK_12") (pintype "input"))
    )
    (net (code "46") (name "/panel_1") (class "Default")
      (node (ref "XP1") (pin "B1") (pinfunction "B1_B1") (pintype "passive"))
      (node (ref "XP1") (pin "B2") (pinfunction "B2_B2") (pintype "passive"))
    )
    (net (code "47") (name "/panel_2") (class "Default")
      (node (ref "XP1") (pin "B3") (pinfunction "B3_B3") (pintype "passive"))
      (node (ref "XP1") (pin "B4") (pinfunction "B4_B4") (pintype "passive"))
    )
    (net (code "48") (name "/panel_3") (class "Default")
      (node (ref "XP1") (pin "B5") (pinfunction "B5_B5") (pintype "passive"))
      (node (ref "XP1") (pin "B6") (pinfunction "B6_B6") (pintype "passive"))
    )
    (net (code "49") (name "/panel_4") (class "Default")
      (node (ref "XP1") (pin "B7") (pinfunction "B7_B7") (pintype "passive"))
      (node (ref "XP1") (pin "B8") (pinfunction "B8_B8") (pintype "passive"))
    )
    (net (code "50") (name "/panel_5") (class "Default")
      (node (ref "XP1") (pin "B10") (pinfunction "B10_B10") (pintype "passive"))
      (node (ref "XP1") (pin "B9") (pinfunction "B9_B9") (pintype "passive"))
    )
    (net (code "51") (name "/panel_6") (class "Default")
      (node (ref "XP1") (pin "B11") (pinfunction "B11_B11") (pintype "passive"))
      (node (ref "XP1") (pin "B12") (pinfunction "B12_B12") (pintype "passive"))
    )
    (net (code "52") (name "/panel_7") (class "Default")
      (node (ref "XP1") (pin "B13") (pinfunction "B13_B13") (pintype "passive"))
      (node (ref "XP1") (pin "B14") (pinfunction "B14_B14") (pintype "passive"))
    )
    (net (code "55") (name "/reset") (class "Default")
      (node (ref "DD2") (pin "12") (pinfunction "D9_12") (pintype "bidirectional"))
      (node (ref "DD2") (pin "3") (pinfunction "RESET_3") (pintype "input"))
    )
    (net (code "57") (name "/voltage_1") (class "Default")
      (node (ref "DD7") (pin "13") (pinfunction "Y0_13") (pintype "passive"))
    )
    (net (code "58") (name "/voltage_2") (class "Default")
      (node (ref "DD7") (pin "14") (pinfunction "Y1_14") (pintype "passive"))
    )
    (net (code "59") (name "/voltage_3") (class "Default")
      (node (ref "DD7") (pin "15") (pinfunction "Y2_15") (pintype "passive"))
    )
    (net (code "60") (name "/voltage_4") (class "Default")
      (node (ref "DD7") (pin "12") (pinfunction "Y3_12") (pintype "passive"))
    )
    (net (code "61") (name "/voltage_5") (class "Default")
      (node (ref "DD7") (pin "1") (pinfunction "Y4_1") (pintype "passive"))
    )
    (net (code "62") (name "/voltage_6") (class "Default")
      (node (ref "DD7") (pin "2") (pinfunction "Y6_2") (pintype "passive"))
    )
    (net (code "63") (name "/voltage_7") (class "Default")
      (node (ref "DD7") (pin "5") (pinfunction "Y5_5") (pintype "passive"))
    )
    (net (code "66") (name "GND") (class "Default")
      (node (ref "C1") (pin "2") (pinfunction "2_2") (pintype "passive"))
      (node (ref "C10") (pin "2") (pinfunction "2_2") (pintype "passive"))
      (node (ref "C11") (pin "1") (pinfunction "1_1") (pintype "passive"))
      (node (ref "C12") (pin "1") (pinfunction "1_1") (pintype "passive"))
      (node (ref "C13") (pin "1") (pinfunction "1_1") (pintype "passive"))
      (node (ref "C14") (pin "1") (pinfunction "1_1") (pintype "passive"))
      (node (ref "C15") (pin "1") (pinfunction "1_1") (pintype "passive"))
      (node (ref "C16") (pin "1") (pinfunction "1_1") (pintype "passive"))
      (node (ref "C2") (pin "2") (pinfunction "2_2") (pintype "passive"))
      (node (ref "C3") (pin "1") (pinfunction "1_1") (pintype "passive"))
      (node (ref "C4") (pin "2") (pinfunction "2_2") (pintype "passive"))
      (node (ref "C5") (pin "1") (pinfunction "1_1") (pintype "passive"))
      (node (ref "C6") (pin "1") (pinfunction "1_1") (pintype "passive"))
      (node (ref "C7") (pin "1") (pinfunction "1_1") (pintype "passive"))
      (node (ref "C8") (pin "1") (pinfunction "1_1") (pintype "passive"))
      (node (ref "C9") (pin "1") (pinfunction "1_1") (pintype "passive"))
      (node (ref "D1") (pin "3") (pinfunction "16_3") (pintype "passive"))
      (node (ref "D2") (pin "3") (pinfunction "16_3") (pintype "passive"))
      (node (ref "DA1") (pin "3") (pinfunction "GND_3") (pintype "passive"))
      (node (ref "DA2") (pin "3") (pinfunction "GND_3") (pintype "passive"))
      (node (ref "DD1") (pin "2") (pinfunction "GND_2") (pintype "passive"))
      (node (ref "DD1") (pin "6") (pinfunction "GND_6") (pintype "passive"))
      (node (ref "DD2") (pin "29") (pinfunction "COM/GND_29") (pintype "power_in"))
      (node (ref "DD2") (pin "4") (pinfunction "COM/GND_4") (pintype "power_in"))
      (node (ref "DD3") (pin "13") (pinfunction "~{OE}_13") (pintype "input"))
      (node (ref "DD3") (pin "8") (pinfunction "GND_8") (pintype "power_in"))
      (node (ref "DD4") (pin "5") (pinfunction "GND_5") (pintype "passive"))
      (node (ref "DD5") (pin "13") (pinfunction "~{OE}_13") (pintype "input"))
      (node (ref "DD5") (pin "8") (pinfunction "GND_8") (pintype "power_in"))
      (node (ref "DD6") (pin "2") (pinfunction "GND1_2") (pintype "passive"))
      (node (ref "DD6") (pin "9") (pinfunction "GND2_9") (pintype "passive"))
      (node (ref "DD7") (pin "6") (pinfunction "~{E}_6") (pintype "passive"))
      (node (ref "DD7") (pin "8") (pinfunction "GND_8") (pintype "passive"))
      (node (ref "DD8") (pin "GND") (pinfunction "GND_GND") (pintype "power_in"))
      (node (ref "R10") (pin "1") (pinfunction "1_1") (pintype "passive"))
      (node (ref "R11") (pin "1") (pinfunction "1_1") (pintype "passive"))
      (node (ref "R15") (pin "1") (pinfunction "1_1") (pintype "passive"))
      (node (ref "R22") (pin "1") (pinfunction "1_1") (pintype "passive"))
      (node (ref "R23") (pin "1") (pinfunction "1_1") (pintype "passive"))
      (node (ref "R24") (pin "1") (pinfunction "1_1") (pintype "passive"))
      (node (ref "R25") (pin "1") (pinfunction "1_1") (pintype "passive"))
      (node (ref "R26") (pin "1") (pinfunction "1_1") (pintype "passive"))
      (node (ref "U1") (pin "3") (pinfunction "3_3") (pintype "passive"))
      (node (ref "VD1") (pin "1") (pinfunction "1_1") (pintype "passive"))
      (node (ref "VD10") (pin "1") (pinfunction "1_1") (pintype "passive"))
      (node (ref "VD11") (pin "1") (pinfunction "1_1") (pintype "passive"))
      (node (ref "VD2") (pin "1") (pinfunction "1_1") (pintype "passive"))
      (node (ref "VD4") (pin "1") (pinfunction "1_1") (pintype "passive"))
      (node (ref "VD5") (pin "1") (pinfunction "1_1") (pintype "passive"))
      (node (ref "VD6") (pin "1") (pinfunction "1_1") (pintype "passive"))
      (node (ref "VD7") (pin "1") (pinfunction "1_1") (pintype "passive"))
      (node (ref "VD8") (pin "1") (pinfunction "1_1") (pintype "passive"))
      (node (ref "VD9") (pin "1") (pinfunction "1_1") (pintype "passive"))
      (node (ref "X1") (pin "N") (pinfunction "N_N") (pintype "passive"))
      (node (ref "XP1") (pin "A16") (pinfunction "A16_A16") (pintype "passive"))
      (node (ref "XP1") (pin "B15") (pinfunction "B15_B15") (pintype "passive"))
      (node (ref "XP1") (pin "B16") (pinfunction "B16_B16") (pintype "passive"))
    )
    (net (code "67") (name "Net-(DA1-MultiSense)") (class "Default")
      (node (ref "DA1") (pin "4") (pinfunction "MultiSense_4") (pintype "passive"))
      (node (ref "R25") (pin "2") (pinfunction "2_2") (pintype "passive"))
    )
    (net (code "68") (name "Net-(DA1-SEn)") (class "Default")
      (node (ref "DA1") (pin "2") (pinfunction "SEn_2") (pintype "passive"))
      (node (ref "R23") (pin "2") (pinfunction "2_2") (pintype "passive"))
    )
    (net (code "69") (name "Net-(DA2-MultiSense)") (class "Default")
      (node (ref "DA2") (pin "4") (pinfunction "MultiSense_4") (pintype "passive"))
      (node (ref "R26") (pin "2") (pinfunction "2_2") (pintype "passive"))
    )
    (net (code "70") (name "Net-(DA2-SEn)") (class "Default")
      (node (ref "DA2") (pin "2") (pinfunction "SEn_2") (pintype "passive"))
      (node (ref "R24") (pin "2") (pinfunction "2_2") (pintype "passive"))
    )
    (net (code "71") (name "Net-(DD1-rx)") (class "Default")
      (node (ref "DD1") (pin "3") (pinfunction "rx_3") (pintype "passive"))
      (node (ref "DD2") (pin "2") (pinfunction "D0/RX_2") (pintype "bidirectional"))
    )
    (net (code "72") (name "Net-(DD1-tx)") (class "Default")
      (node (ref "DD1") (pin "4") (pinfunction "tx_4") (pintype "passive"))
      (node (ref "DD2") (pin "1") (pinfunction "D1/TX_1") (pintype "bidirectional"))
    )
    (net (code "73") (name "Net-(DD2-A5)") (class "Default")
      (node (ref "DD2") (pin "24") (pinfunction "A5_24") (pintype "input"))
      (node (ref "SB1") (pin "2") (pinfunction "2_2") (pintype "passive"))
    )
    (net (code "74") (name "Net-(DD2-A6)") (class "Default")
      (node (ref "DD2") (pin "25") (pinfunction "A6_25") (pintype "input"))
      (node (ref "SB2") (pin "2") (pinfunction "2_2") (pintype "passive"))
    )
    (net (code "75") (name "Net-(DD2-A7)") (class "Default")
      (node (ref "DD2") (pin "26") (pinfunction "A7_26") (pintype "input"))
      (node (ref "SB3") (pin "2") (pinfunction "2_2") (pintype "passive"))
    )
    (net (code "76") (name "Net-(DD2-D3)") (class "Default")
      (node (ref "DD2") (pin "6") (pinfunction "D3_6") (pintype "bidirectional"))
      (node (ref "DD6") (pin "3") (pinfunction "RX_3") (pintype "passive"))
    )
    (net (code "77") (name "Net-(DD2-D4)") (class "Default")
      (node (ref "DD2") (pin "7") (pinfunction "D4_7") (pintype "bidirectional"))
      (node (ref "DD6") (pin "4") (pinfunction "~{RE}_4") (pintype "passive"))
      (node (ref "DD6") (pin "5") (pinfunction "DE_5") (pintype "passive"))
    )
    (net (code "78") (name "Net-(DD2-D5)") (class "Default")
      (node (ref "DD2") (pin "8") (pinfunction "D5_8") (pintype "bidirectional"))
      (node (ref "DD6") (pin "6") (pinfunction "TX_6") (pintype "passive"))
    )
    (net (code "79") (name "Net-(DD2-D7)") (class "Default")
      (node (ref "DD2") (pin "10") (pinfunction "D7_10") (pintype "bidirectional"))
      (node (ref "DD3") (pin "14") (pinfunction "A_14") (pintype "input"))
    )
    (net (code "80") (name "Net-(DD2-D10)") (class "Default")
      (node (ref "DD2") (pin "13") (pinfunction "D10_13") (pintype "bidirectional"))
      (node (ref "DD3") (pin "11") (pinfunction "SHIFT_CLK_11") (pintype "input"))
      (node (ref "DD5") (pin "11") (pinfunction "SHIFT_CLK_11") (pintype "input"))
    )
    (net (code "81") (name "Net-(DD2-D11{slash}MOSI)") (class "Default")
      (node (ref "DD2") (pin "14") (pinfunction "D11/MOSI_14") (pintype "bidirectional"))
      (node (ref "DD7") (pin "11") (pinfunction "S0_11") (pintype "passive"))
    )
    (net (code "82") (name "Net-(DD2-D12{slash}MISO)") (class "Default")
      (node (ref "DD2") (pin "15") (pinfunction "D12/MISO_15") (pintype "bidirectional"))
      (node (ref "DD7") (pin "10") (pinfunction "S1_10") (pintype "passive"))
    )
    (net (code "83") (name "Net-(DD2-D13{slash}SCK)") (class "Default")
      (node (ref "DD2") (pin "16") (pinfunction "D13/SCK_16") (pintype "bidirectional"))
      (node (ref "DD7") (pin "9") (pinfunction "S2_9") (pintype "passive"))
    )
    (net (code "84") (name "Net-(DD3-SQH)") (class "Default")
      (node (ref "DD3") (pin "9") (pinfunction "SQH_9") (pintype "output"))
      (node (ref "DD5") (pin "14") (pinfunction "A_14") (pintype "input"))
    )
    (net (code "85") (name "Net-(DD4-DE)") (class "Default")
      (node (ref "DD4") (pin "2") (pinfunction "RE_2") (pintype "passive"))
      (node (ref "DD4") (pin "3") (pinfunction "DE_3") (pintype "passive"))
      (node (ref "SB2") (pin "1") (pinfunction "1_1") (pintype "passive"))
    )
    (net (code "86") (name "Net-(DD4-DI)") (class "Default")
      (node (ref "DD4") (pin "4") (pinfunction "DI_4") (pintype "passive"))
      (node (ref "SB3") (pin "1") (pinfunction "1_1") (pintype "passive"))
    )
    (net (code "87") (name "Net-(DD4-RO)") (class "Default")
      (node (ref "DD4") (pin "1") (pinfunction "RO_1") (pintype "passive"))
      (node (ref "SB1") (pin "1") (pinfunction "1_1") (pintype "passive"))
    )
    (net (code "88") (name "Net-(DD7-Y7)") (class "Default")
      (node (ref "C15") (pin "2") (pinfunction "2_2") (pintype "passive"))
      (node (ref "DD7") (pin "4") (pinfunction "Y7_4") (pintype "passive"))
      (node (ref "R21") (pin "1") (pinfunction "1_1") (pintype "passive"))
      (node (ref "R22") (pin "2") (pinfunction "2_2") (pintype "passive"))
    )
    (net (code "89") (name "Net-(F1-Pad1)") (class "Default")
      (node (ref "F1") (pin "1") (pinfunction "1_1") (pintype "passive"))
      (node (ref "X1") (pin "P") (pinfunction "P_P") (pintype "passive"))
    )
    (net (code "90") (name "Net-(R2-Pad1)") (class "Default")
      (node (ref "R2") (pin "1") (pinfunction "1_1") (pintype "passive"))
      (node (ref "VT1") (pin "2") (pinfunction "2_2") (pintype "passive"))
    )
    (net (code "91") (name "Net-(R9-Pad2)") (class "Default")
      (node (ref "R9") (pin "2") (pinfunction "2_2") (pintype "passive"))
      (node (ref "XP1") (pin "A8") (pinfunction "A8_A8") (pintype "passive"))
    )
    (net (code "92") (name "Net-(R10-Pad2)") (class "Default")
      (node (ref "R10") (pin "2") (pinfunction "2_2") (pintype "passive"))
      (node (ref "R4") (pin "1") (pinfunction "1_1") (pintype "passive"))
      (node (ref "U1") (pin "1") (pinfunction "1_1") (pintype "passive"))
    )
    (net (code "93") (name "Net-(R11-Pad2)") (class "Default")
      (node (ref "R11") (pin "2") (pinfunction "2_2") (pintype "passive"))
      (node (ref "VD3") (pin "1") (pinfunction "1_1") (pintype "passive"))
      (node (ref "VT1") (pin "1") (pinfunction "1_1") (pintype "passive"))
    )
    (net (code "94") (name "Net-(R12-Pad2)") (class "Default")
      (node (ref "R12") (pin "2") (pinfunction "2_2") (pintype "passive"))
      (node (ref "XP1") (pin "A10") (pinfunction "A10_A10") (pintype "passive"))
    )
    (net (code "95") (name "Net-(R13-Pad2)") (class "Default")
      (node (ref "R13") (pin "2") (pinfunction "2_2") (pintype "passive"))
      (node (ref "XP1") (pin "A11") (pinfunction "A11_A11") (pintype "passive"))
    )
    (net (code "96") (name "Net-(R14-Pad2)") (class "Default")
      (node (ref "R14") (pin "2") (pinfunction "2_2") (pintype "passive"))
      (node (ref "XP1") (pin "A12") (pinfunction "A12_A12") (pintype "passive"))
    )
    (net (code "97") (name "Net-(R16-Pad2)") (class "Default")
      (node (ref "R16") (pin "2") (pinfunction "2_2") (pintype "passive"))
      (node (ref "XP1") (pin "A13") (pinfunction "A13_A13") (pintype "passive"))
    )
    (net (code "98") (name "Net-(R17-Pad2)") (class "Default")
      (node (ref "R17") (pin "2") (pinfunction "2_2") (pintype "passive"))
      (node (ref "XP1") (pin "A14") (pinfunction "A14_A14") (pintype "passive"))
    )
    (net (code "99") (name "Net-(R18-Pad2)") (class "Default")
      (node (ref "R18") (pin "2") (pinfunction "2_2") (pintype "passive"))
      (node (ref "XP1") (pin "A15") (pinfunction "A15_A15") (pintype "passive"))
    )
    (net (code "100") (name "unconnected-(DD1-RST-Pad1)") (class "Default")
      (node (ref "DD1") (pin "1") (pinfunction "RST_1") (pintype "passive+no_connect"))
    )
    (net (code "101") (name "unconnected-(DD1-VDD-Pad5)") (class "Default")
      (node (ref "DD1") (pin "5") (pinfunction "VDD_5") (pintype "passive+no_connect"))
    )
    (net (code "102") (name "unconnected-(DD2-AREF-Pad18)") (class "Default")
      (node (ref "DD2") (pin "18") (pinfunction "AREF_18") (pintype "power_in"))
    )
    (net (code "103") (name "unconnected-(DD2-RESET-Pad28)") (class "Default")
      (node (ref "DD2") (pin "28") (pinfunction "RESET_28") (pintype "input+no_connect"))
    )
    (net (code "104") (name "unconnected-(DD2-VIN-Pad30)") (class "Default")
      (node (ref "DD2") (pin "30") (pinfunction "VIN_30") (pintype "input+no_connect"))
    )
    (net (code "105") (name "unconnected-(DD5-QF-Pad5)") (class "Default")
      (node (ref "DD5") (pin "5") (pinfunction "QF_5") (pintype "output+no_connect"))
    )
    (net (code "106") (name "unconnected-(DD5-QG-Pad6)") (class "Default")
      (node (ref "DD5") (pin "6") (pinfunction "QG_6") (pintype "output+no_connect"))
    )
    (net (code "107") (name "unconnected-(DD5-QH-Pad7)") (class "Default")
      (node (ref "DD5") (pin "7") (pinfunction "QH_7") (pintype "output+no_connect"))
    )
    (net (code "108") (name "unconnected-(DD5-SQH-Pad9)") (class "Default")
      (node (ref "DD5") (pin "9") (pinfunction "SQH_9") (pintype "output+no_connect"))
    )
    (net (code "109") (name "unconnected-(DD8-NULL-PadNC)") (class "Default")
      (node (ref "DD8") (pin "NC") (pinfunction "NULL_NC") (pintype "passive"))
    )
  )
)
